# power_mux-fpf1320.net
KiCad netlist of a schematic drawn in EAGLE
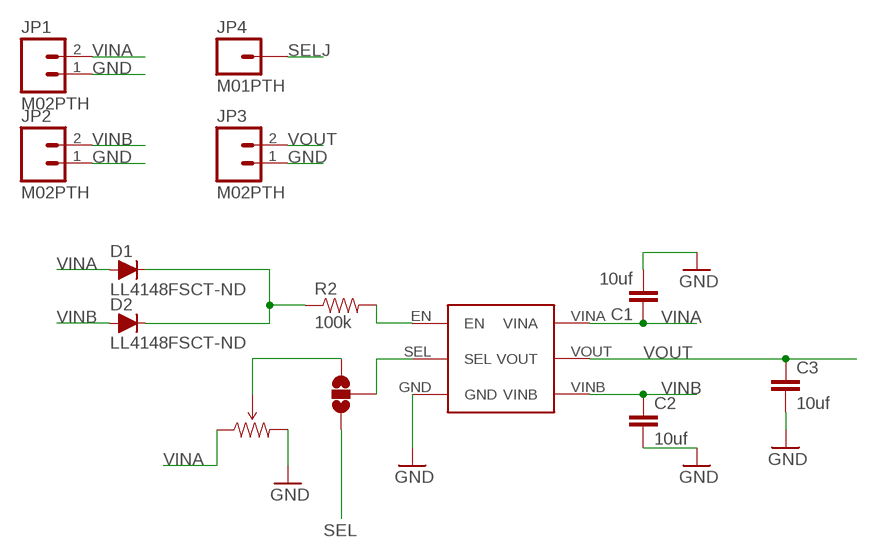
[diagram p0: schematic, sheet 1]

(export (version "E")
  (design (tool "Eeschema 10.0.6"))
  (components
    (comp (ref "C1")
      (value "10uf")
      (footprint "eagle-import:0805")
      (libsource (lib "eagle-import") (part "CAP0805"))
    )
    (comp (ref "C2")
      (value "10uf")
      (footprint "eagle-import:0805")
      (libsource (lib "eagle-import") (part "CAP0805"))
    )
    (comp (ref "C3")
      (value "10uf")
      (footprint "eagle-import:0805")
      (libsource (lib "eagle-import") (part "CAP0805"))
    )
    (comp (ref "D1")
      (value "LL4148FSCT-ND")
      (footprint "eagle-import:SOD80")
      (libsource (lib "eagle-import") (part "D-FILL-SOD-80"))
    )
    (comp (ref "D2")
      (value "LL4148FSCT-ND")
      (footprint "eagle-import:SOD80")
      (libsource (lib "eagle-import") (part "D-FILL-SOD-80"))
    )
    (comp (ref "JP1")
      (value "M02PTH")
      (footprint "eagle-import:1X02")
      (libsource (lib "eagle-import") (part "M02PTH"))
    )
    (comp (ref "JP2")
      (value "M02PTH")
      (footprint "eagle-import:1X02")
      (libsource (lib "eagle-import") (part "M02PTH"))
    )
    (comp (ref "JP3")
      (value "M02PTH")
      (footprint "eagle-import:1X02")
      (libsource (lib "eagle-import") (part "M02PTH"))
    )
    (comp (ref "JP4")
      (value "M01PTH")
      (footprint "eagle-import:1X01")
      (libsource (lib "eagle-import") (part "M01PTH"))
    )
    (comp (ref "R1")
      (value "TRIMPOT-PTH-KNOB")
      (footprint "eagle-import:3386U")
      (libsource (lib "eagle-import") (part "TRIMPOT-PTH-KNOB"))
    )
    (comp (ref "R2")
      (value "100k")
      (footprint "eagle-import:0805")
      (libsource (lib "eagle-import") (part "RESISTOR0805-RES"))
    )
    (comp (ref "SJ2")
      (value "SOLDERJUMPER_2WAYPASTE1&2")
      (footprint "eagle-import:SJ_3_PASTE1&2")
      (libsource (lib "eagle-import") (part "SOLDERJUMPER_2WAYPASTE1&2"))
    )
    (comp (ref "U$3")
      (value "FPF1320")
      (footprint "eagle-import:6-UFBGA")
      (libsource (lib "eagle-import") (part "FPF1320"))
    )
  )
  (nets
    (net (code "1") (name "/SEL") (class "Default")
      (node (ref "R1") (pin "2") (pinfunction "WIPER_2") (pintype "passive"))
      (node (ref "SJ2") (pin "3") (pinfunction "3_3") (pintype "passive"))
    )
    (net (code "2") (name "/SELJ") (class "Default")
      (node (ref "JP4") (pin "1") (pinfunction "1_1") (pintype "passive"))
      (node (ref "SJ2") (pin "1") (pinfunction "1_1") (pintype "passive"))
    )
    (net (code "3") (name "/VINA") (class "Default")
      (node (ref "C1") (pin "1") (pinfunction "1_1") (pintype "passive"))
      (node (ref "D1") (pin "2") (pinfunction "A_2") (pintype "passive"))
      (node (ref "JP1") (pin "2") (pinfunction "2_2") (pintype "passive"))
      (node (ref "R1") (pin "1") (pinfunction "CCW_1") (pintype "passive"))
      (node (ref "U$3") (pin "VINA") (pinfunction "VINA_VINA") (pintype "bidirectional"))
    )
    (net (code "4") (name "/VINB") (class "Default")
      (node (ref "C2") (pin "1") (pinfunction "1_1") (pintype "passive"))
      (node (ref "D2") (pin "2") (pinfunction "A_2") (pintype "passive"))
      (node (ref "JP2") (pin "2") (pinfunction "2_2") (pintype "passive"))
      (node (ref "U$3") (pin "VINB") (pinfunction "VINB_VINB") (pintype "bidirectional"))
    )
    (net (code "5") (name "/VOUT") (class "Default")
      (node (ref "C3") (pin "1") (pinfunction "1_1") (pintype "passive"))
      (node (ref "JP3") (pin "2") (pinfunction "2_2") (pintype "passive"))
      (node (ref "U$3") (pin "VOUT") (pinfunction "VOUT_VOUT") (pintype "bidirectional"))
    )
    (net (code "6") (name "GND") (class "Default")
      (node (ref "C1") (pin "2") (pinfunction "2_2") (pintype "passive"))
      (node (ref "C2") (pin "2") (pinfunction "2_2") (pintype "passive"))
      (node (ref "C3") (pin "2") (pinfunction "2_2") (pintype "passive"))
      (node (ref "JP1") (pin "1") (pinfunction "1_1") (pintype "passive"))
      (node (ref "JP2") (pin "1") (pinfunction "1_1") (pintype "passive"))
      (node (ref "JP3") (pin "1") (pinfunction "1_1") (pintype "passive"))
      (node (ref "R1") (pin "3") (pinfunction "CW_3") (pintype "passive"))
      (node (ref "U$3") (pin "GND") (pinfunction "GND_GND") (pintype "bidirectional"))
    )
    (net (code "7") (name "Net-(D1-C)") (class "Default")
      (node (ref "D1") (pin "1") (pinfunction "C_1") (pintype "passive"))
      (node (ref "D2") (pin "1") (pinfunction "C_1") (pintype "passive"))
      (node (ref "R2") (pin "1") (pinfunction "1_1") (pintype "passive"))
    )
    (net (code "8") (name "Net-(R2-Pad2)") (class "Default")
      (node (ref "R2") (pin "2") (pinfunction "2_2") (pintype "passive"))
      (node (ref "U$3") (pin "EN") (pinfunction "EN_EN") (pintype "bidirectional"))
    )
    (net (code "9") (name "Net-(SJ2-Pad2)") (class "Default")
      (node (ref "SJ2") (pin "2") (pinfunction "2_2") (pintype "passive"))
      (node (ref "U$3") (pin "SEL") (pinfunction "SEL_SEL") (pintype "bidirectional"))
    )
  )
)
